# cree_module.net
KiCad netlist of a schematic drawn in Altium Designer
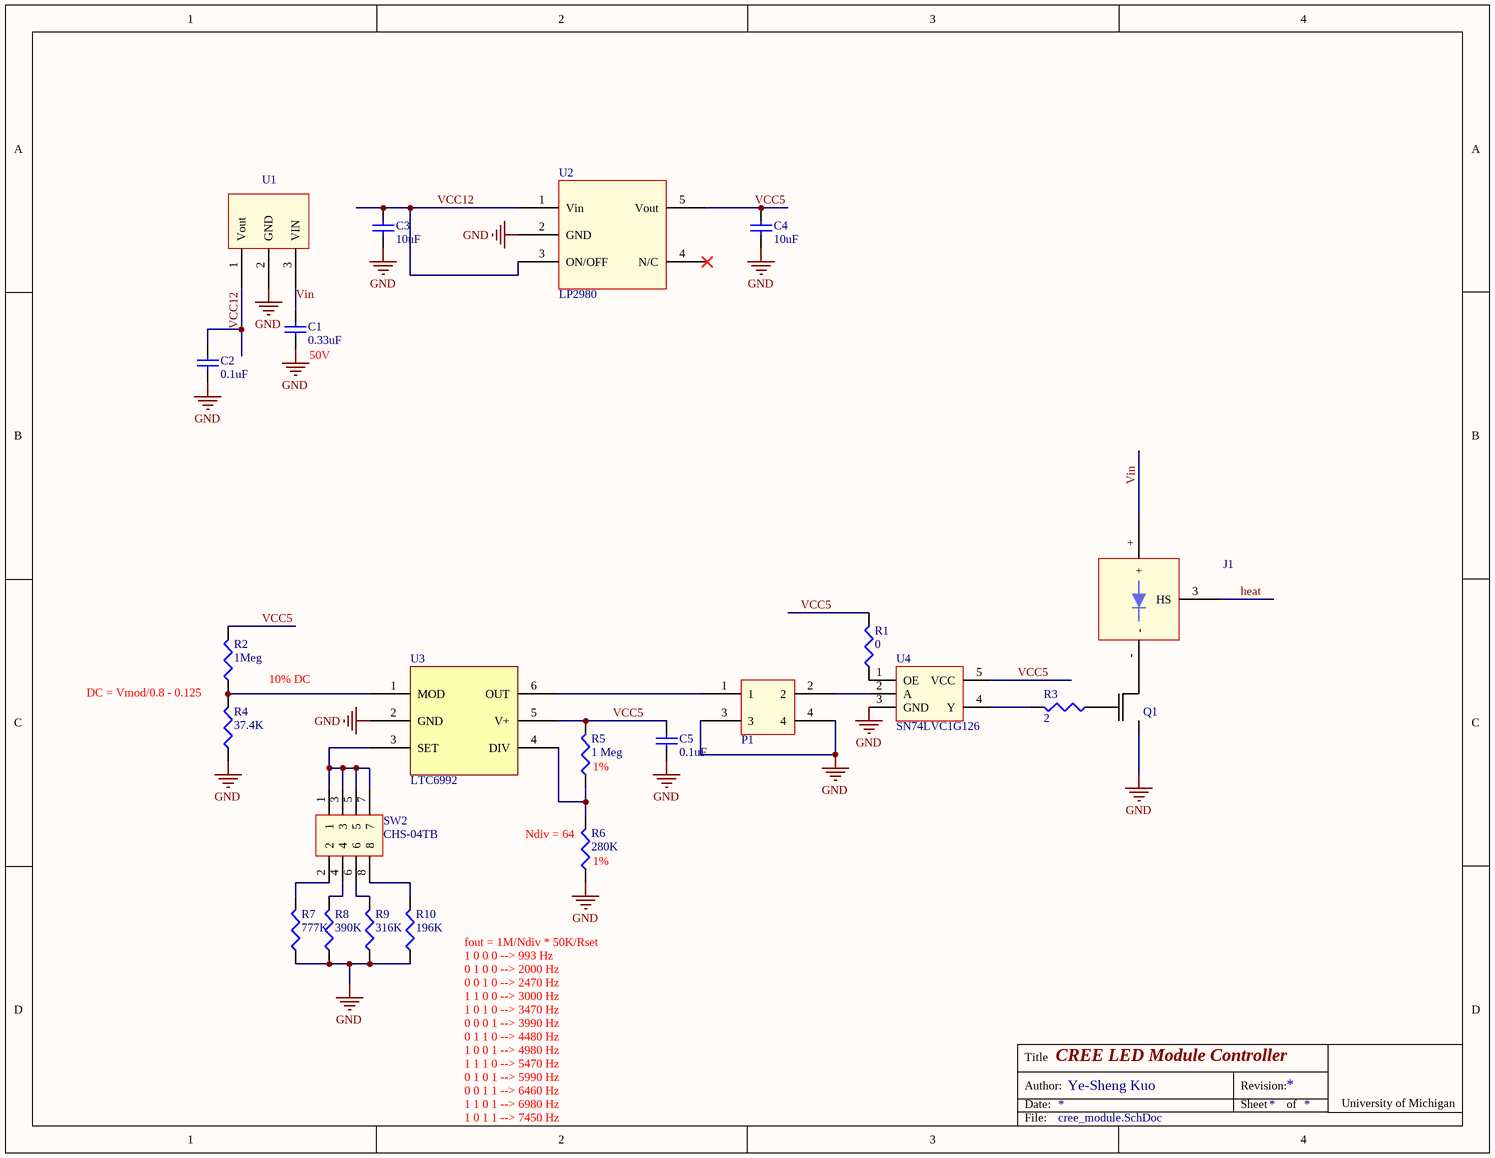
[diagram p0: cree_module.SchDoc]

(export (version "E")
  (design (tool "Eeschema 10.0.6"))
  (components
    (comp (ref "C1")
      (value "0.33uF")
      (footprint "1608[0603]")
      (description "Capacitor (Semiconductor SIM Model)")
      (fields (field (name "Comment") "Cap Semi") (field (name "PUBLISHER") "Altium Limited"))
      (libsource (lib "Miscellaneous Devices") (part "Cap Semi"))
    )
    (comp (ref "C2")
      (value "0.1uF")
      (footprint "1608[0603]")
      (description "Capacitor (Semiconductor SIM Model)")
      (fields (field (name "Comment") "Cap Semi") (field (name "PUBLISHER") "Altium Limited"))
      (libsource (lib "Miscellaneous Devices") (part "Cap Semi"))
    )
    (comp (ref "C3")
      (value "10uF")
      (footprint "1608[0603]")
      (description "Capacitor (Semiconductor SIM Model)")
      (fields (field (name "Comment") "Cap Semi") (field (name "PUBLISHER") "Altium Limited"))
      (libsource (lib "Miscellaneous Devices") (part "Cap Semi"))
    )
    (comp (ref "C4")
      (value "10uF")
      (footprint "1608[0603]")
      (description "Capacitor (Semiconductor SIM Model)")
      (fields (field (name "Comment") "Cap Semi") (field (name "PUBLISHER") "Altium Limited"))
      (libsource (lib "Miscellaneous Devices") (part "Cap Semi"))
    )
    (comp (ref "C5")
      (value "0.1uF")
      (footprint "1608[0603]")
      (description "Capacitor (Semiconductor SIM Model)")
      (fields (field (name "Comment") "Cap Semi") (field (name "PUBLISHER") "Altium Limited"))
      (libsource (lib "Miscellaneous Devices") (part "Cap Semi"))
    )
    (comp (ref "J1")
      (value "1807200002")
      (footprint "molex")
      (description "LED Array Holders  for CREE* XLamp†   Arrays")
      (libsource (lib "vlc_ctrl") (part "Molex LED holder"))
    )
    (comp (ref "P1")
      (value "2 x 2 header SMD")
      (footprint "2x2 header SMD")
      (description "2x2 100 mil header SMD")
      (libsource (lib "vlc_ctrl") (part "2 x 2 header SMD"))
    )
    (comp (ref "Q1")
      (value "Si2312CDS")
      (footprint "SOT95P250-3N")
      (description "N-Channel 20 V (D-S) MOSFET")
      (libsource (lib "vlc_ctrl") (part "Si2312CDS"))
    )
    (comp (ref "R1")
      (value "0")
      (footprint "J1-0603")
      (description "Resistor")
      (fields (field (name "Comment") "Res3") (field (name "PUBLISHER") "Altium Limited"))
      (libsource (lib "Miscellaneous Devices") (part "Res3"))
    )
    (comp (ref "R2")
      (value "1Meg")
      (footprint "J1-0603")
      (description "Resistor")
      (fields (field (name "Comment") "Res3") (field (name "PUBLISHER") "Altium Limited"))
      (libsource (lib "Miscellaneous Devices") (part "Res3"))
    )
    (comp (ref "R3")
      (value "2")
      (footprint "J1-0603")
      (description "Resistor")
      (fields (field (name "Comment") "Res3") (field (name "PUBLISHER") "Altium Limited"))
      (libsource (lib "Miscellaneous Devices") (part "Res3"))
    )
    (comp (ref "R4")
      (value "37.4K")
      (footprint "J1-0603")
      (description "Resistor")
      (fields (field (name "Comment") "Res3") (field (name "PUBLISHER") "Altium Limited"))
      (libsource (lib "Miscellaneous Devices") (part "Res3"))
    )
    (comp (ref "R5")
      (value "1 Meg")
      (footprint "J1-0603")
      (description "Resistor")
      (fields (field (name "Comment") "Res3") (field (name "PUBLISHER") "Altium Limited"))
      (libsource (lib "Miscellaneous Devices") (part "Res3"))
    )
    (comp (ref "R6")
      (value "280K")
      (footprint "J1-0603")
      (description "Resistor")
      (fields (field (name "Comment") "Res3") (field (name "PUBLISHER") "Altium Limited"))
      (libsource (lib "Miscellaneous Devices") (part "Res3"))
    )
    (comp (ref "R7")
      (value "777K")
      (footprint "6-0805_N")
      (description "Resistor")
      (fields (field (name "Comment") "Res3") (field (name "PUBLISHER") "Altium Limited"))
      (libsource (lib "Miscellaneous Devices") (part "Res3"))
    )
    (comp (ref "R8")
      (value "390K")
      (footprint "6-0805_N")
      (description "Resistor")
      (fields (field (name "Comment") "Res3") (field (name "PUBLISHER") "Altium Limited"))
      (libsource (lib "Miscellaneous Devices") (part "Res3"))
    )
    (comp (ref "R9")
      (value "316K")
      (footprint "6-0805_N")
      (description "Resistor")
      (fields (field (name "Comment") "Res3") (field (name "PUBLISHER") "Altium Limited"))
      (libsource (lib "Miscellaneous Devices") (part "Res3"))
    )
    (comp (ref "R10")
      (value "196K")
      (footprint "6-0805_N")
      (description "Resistor")
      (fields (field (name "Comment") "Res3") (field (name "PUBLISHER") "Altium Limited"))
      (libsource (lib "Miscellaneous Devices") (part "Res3"))
    )
    (comp (ref "SW2")
      (value "CHS-04TB")
      (footprint "CHS04TB")
      (description "SLIDE SWITCHES")
      (libsource (lib "vlc_ctrl") (part "CHS-04TB"))
    )
    (comp (ref "U1")
      (value "L78L")
      (footprint "SOT89-150P409X160-3N")
      (description "Positive voltage regulators")
      (libsource (lib "vlc_ctrl") (part "L78L"))
    )
    (comp (ref "U2")
      (value "LP2980")
      (footprint "SOT23-5")
      (description "LP2980-N Micropower 50 mA Ultra Low-Dropout Regulator In SOT-23 Package")
      (libsource (lib "vlc_ctrl") (part "LP2980-N"))
    )
    (comp (ref "U3")
      (value "LTC6992")
      (footprint "TSOT23-6")
      (description "TimerBlox: Voltage-Controlled Pulse   Width Modulator (PWM)")
      (libsource (lib "VLC") (part "LTC6992"))
    )
    (comp (ref "U4")
      (value "SN74LVC1G126")
      (footprint "SOT23-5")
      (description "Single Bus Buffer Gate With 3-State Output")
      (libsource (lib "vlc_ctrl") (part "SN74LVC1G126"))
    )
  )
  (nets
    (net (code "1") (name "/VCC5") (class "Default")
      (node (ref "C4") (pin "2") (pinfunction "2_2") (pintype "passive"))
      (node (ref "C5") (pin "2") (pinfunction "2_2") (pintype "passive"))
      (node (ref "R1") (pin "2") (pinfunction "2_2") (pintype "passive"))
      (node (ref "R2") (pin "2") (pinfunction "2_2") (pintype "passive"))
      (node (ref "R5") (pin "2") (pinfunction "2_2") (pintype "passive"))
      (node (ref "U2") (pin "5") (pinfunction "Vout_5") (pintype "passive"))
      (node (ref "U3") (pin "5") (pinfunction "V+_5") (pintype "passive"))
      (node (ref "U4") (pin "5") (pinfunction "VCC_5") (pintype "passive"))
    )
    (net (code "2") (name "/VCC12") (class "Default")
      (node (ref "C2") (pin "2") (pinfunction "2_2") (pintype "passive"))
      (node (ref "C3") (pin "2") (pinfunction "2_2") (pintype "passive"))
      (node (ref "U1") (pin "1") (pinfunction "Vout_1") (pintype "passive"))
      (node (ref "U2") (pin "1") (pinfunction "Vin_1") (pintype "passive"))
      (node (ref "U2") (pin "3") (pinfunction "ON/OFF_3") (pintype "passive"))
    )
    (net (code "3") (name "/Vin") (class "Default")
      (node (ref "C1") (pin "2") (pinfunction "2_2") (pintype "passive"))
      (node (ref "J1") (pin "+") (pinfunction "+_+") (pintype "passive"))
      (node (ref "U1") (pin "3") (pinfunction "VIN_3") (pintype "passive"))
    )
    (net (code "4") (name "/heat") (class "Default")
      (node (ref "J1") (pin "3") (pinfunction "HS_3") (pintype "passive"))
    )
    (net (code "5") (name "GND") (class "Default")
      (node (ref "C1") (pin "1") (pinfunction "1_1") (pintype "passive"))
      (node (ref "C2") (pin "1") (pinfunction "1_1") (pintype "passive"))
      (node (ref "C3") (pin "1") (pinfunction "1_1") (pintype "passive"))
      (node (ref "C4") (pin "1") (pinfunction "1_1") (pintype "passive"))
      (node (ref "C5") (pin "1") (pinfunction "1_1") (pintype "passive"))
      (node (ref "P1") (pin "3") (pinfunction "3_3") (pintype "passive"))
      (node (ref "P1") (pin "4") (pinfunction "4_4") (pintype "passive"))
      (node (ref "Q1") (pin "2") (pinfunction "S_2") (pintype "passive"))
      (node (ref "R10") (pin "1") (pinfunction "1_1") (pintype "passive"))
      (node (ref "R4") (pin "1") (pinfunction "1_1") (pintype "passive"))
      (node (ref "R6") (pin "1") (pinfunction "1_1") (pintype "passive"))
      (node (ref "R7") (pin "1") (pinfunction "1_1") (pintype "passive"))
      (node (ref "R8") (pin "1") (pinfunction "1_1") (pintype "passive"))
      (node (ref "R9") (pin "1") (pinfunction "1_1") (pintype "passive"))
      (node (ref "U1") (pin "2") (pinfunction "GND_2") (pintype "passive"))
      (node (ref "U2") (pin "2") (pinfunction "GND_2") (pintype "passive"))
      (node (ref "U3") (pin "2") (pinfunction "GND_2") (pintype "passive"))
      (node (ref "U4") (pin "3") (pinfunction "GND_3") (pintype "passive"))
    )
    (net (code "6") (name "Net-(Q1-D)") (class "Default")
      (node (ref "J1") (pin "-") (pinfunction "-_-") (pintype "passive"))
      (node (ref "Q1") (pin "3") (pinfunction "D_3") (pintype "passive"))
    )
    (net (code "7") (name "Net-(Q1-G)") (class "Default")
      (node (ref "Q1") (pin "1") (pinfunction "G_1") (pintype "passive"))
      (node (ref "R3") (pin "1") (pinfunction "1_1") (pintype "passive"))
    )
    (net (code "8") (name "Net-(R7-Pad2)") (class "Default")
      (node (ref "R7") (pin "2") (pinfunction "2_2") (pintype "passive"))
      (node (ref "SW2") (pin "2") (pinfunction "2_2") (pintype "passive"))
    )
    (net (code "9") (name "Net-(R8-Pad2)") (class "Default")
      (node (ref "R8") (pin "2") (pinfunction "2_2") (pintype "passive"))
      (node (ref "SW2") (pin "4") (pinfunction "4_4") (pintype "passive"))
    )
    (net (code "10") (name "Net-(R9-Pad2)") (class "Default")
      (node (ref "R9") (pin "2") (pinfunction "2_2") (pintype "passive"))
      (node (ref "SW2") (pin "6") (pinfunction "6_6") (pintype "passive"))
    )
    (net (code "11") (name "Net-(R10-Pad2)") (class "Default")
      (node (ref "R10") (pin "2") (pinfunction "2_2") (pintype "passive"))
      (node (ref "SW2") (pin "8") (pinfunction "8_8") (pintype "passive"))
    )
    (net (code "12") (name "Net-(U3-DIV)") (class "Default")
      (node (ref "R5") (pin "1") (pinfunction "1_1") (pintype "passive"))
      (node (ref "R6") (pin "2") (pinfunction "2_2") (pintype "passive"))
      (node (ref "U3") (pin "4") (pinfunction "DIV_4") (pintype "passive"))
    )
    (net (code "13") (name "Net-(U3-MOD)") (class "Default")
      (node (ref "R2") (pin "1") (pinfunction "1_1") (pintype "passive"))
      (node (ref "R4") (pin "2") (pinfunction "2_2") (pintype "passive"))
      (node (ref "U3") (pin "1") (pinfunction "MOD_1") (pintype "passive"))
    )
    (net (code "14") (name "Net-(U3-OUT)") (class "Default")
      (node (ref "P1") (pin "1") (pinfunction "1_1") (pintype "passive"))
      (node (ref "U3") (pin "6") (pinfunction "OUT_6") (pintype "passive"))
    )
    (net (code "15") (name "Net-(U3-SET)") (class "Default")
      (node (ref "SW2") (pin "1") (pinfunction "1_1") (pintype "passive"))
      (node (ref "SW2") (pin "3") (pinfunction "3_3") (pintype "passive"))
      (node (ref "SW2") (pin "5") (pinfunction "5_5") (pintype "passive"))
      (node (ref "SW2") (pin "7") (pinfunction "7_7") (pintype "passive"))
      (node (ref "U3") (pin "3") (pinfunction "SET_3") (pintype "passive"))
    )
    (net (code "16") (name "Net-(U4-A)") (class "Default")
      (node (ref "P1") (pin "2") (pinfunction "2_2") (pintype "passive"))
      (node (ref "U4") (pin "2") (pinfunction "A_2") (pintype "passive"))
    )
    (net (code "17") (name "Net-(U4-OE)") (class "Default")
      (node (ref "R1") (pin "1") (pinfunction "1_1") (pintype "passive"))
      (node (ref "U4") (pin "1") (pinfunction "OE_1") (pintype "passive"))
    )
    (net (code "18") (name "Net-(U4-Y)") (class "Default")
      (node (ref "R3") (pin "2") (pinfunction "2_2") (pintype "passive"))
      (node (ref "U4") (pin "4") (pinfunction "Y_4") (pintype "passive"))
    )
    (net (code "19") (name "unconnected-(U2-N{slash}C-Pad4)") (class "Default")
      (node (ref "U2") (pin "4") (pinfunction "N/C_4") (pintype "passive+no_connect"))
    )
  )
)
